# SCH_touch_clock_2022-06-03.net
KiCad netlist of a schematic drawn in EasyEDA
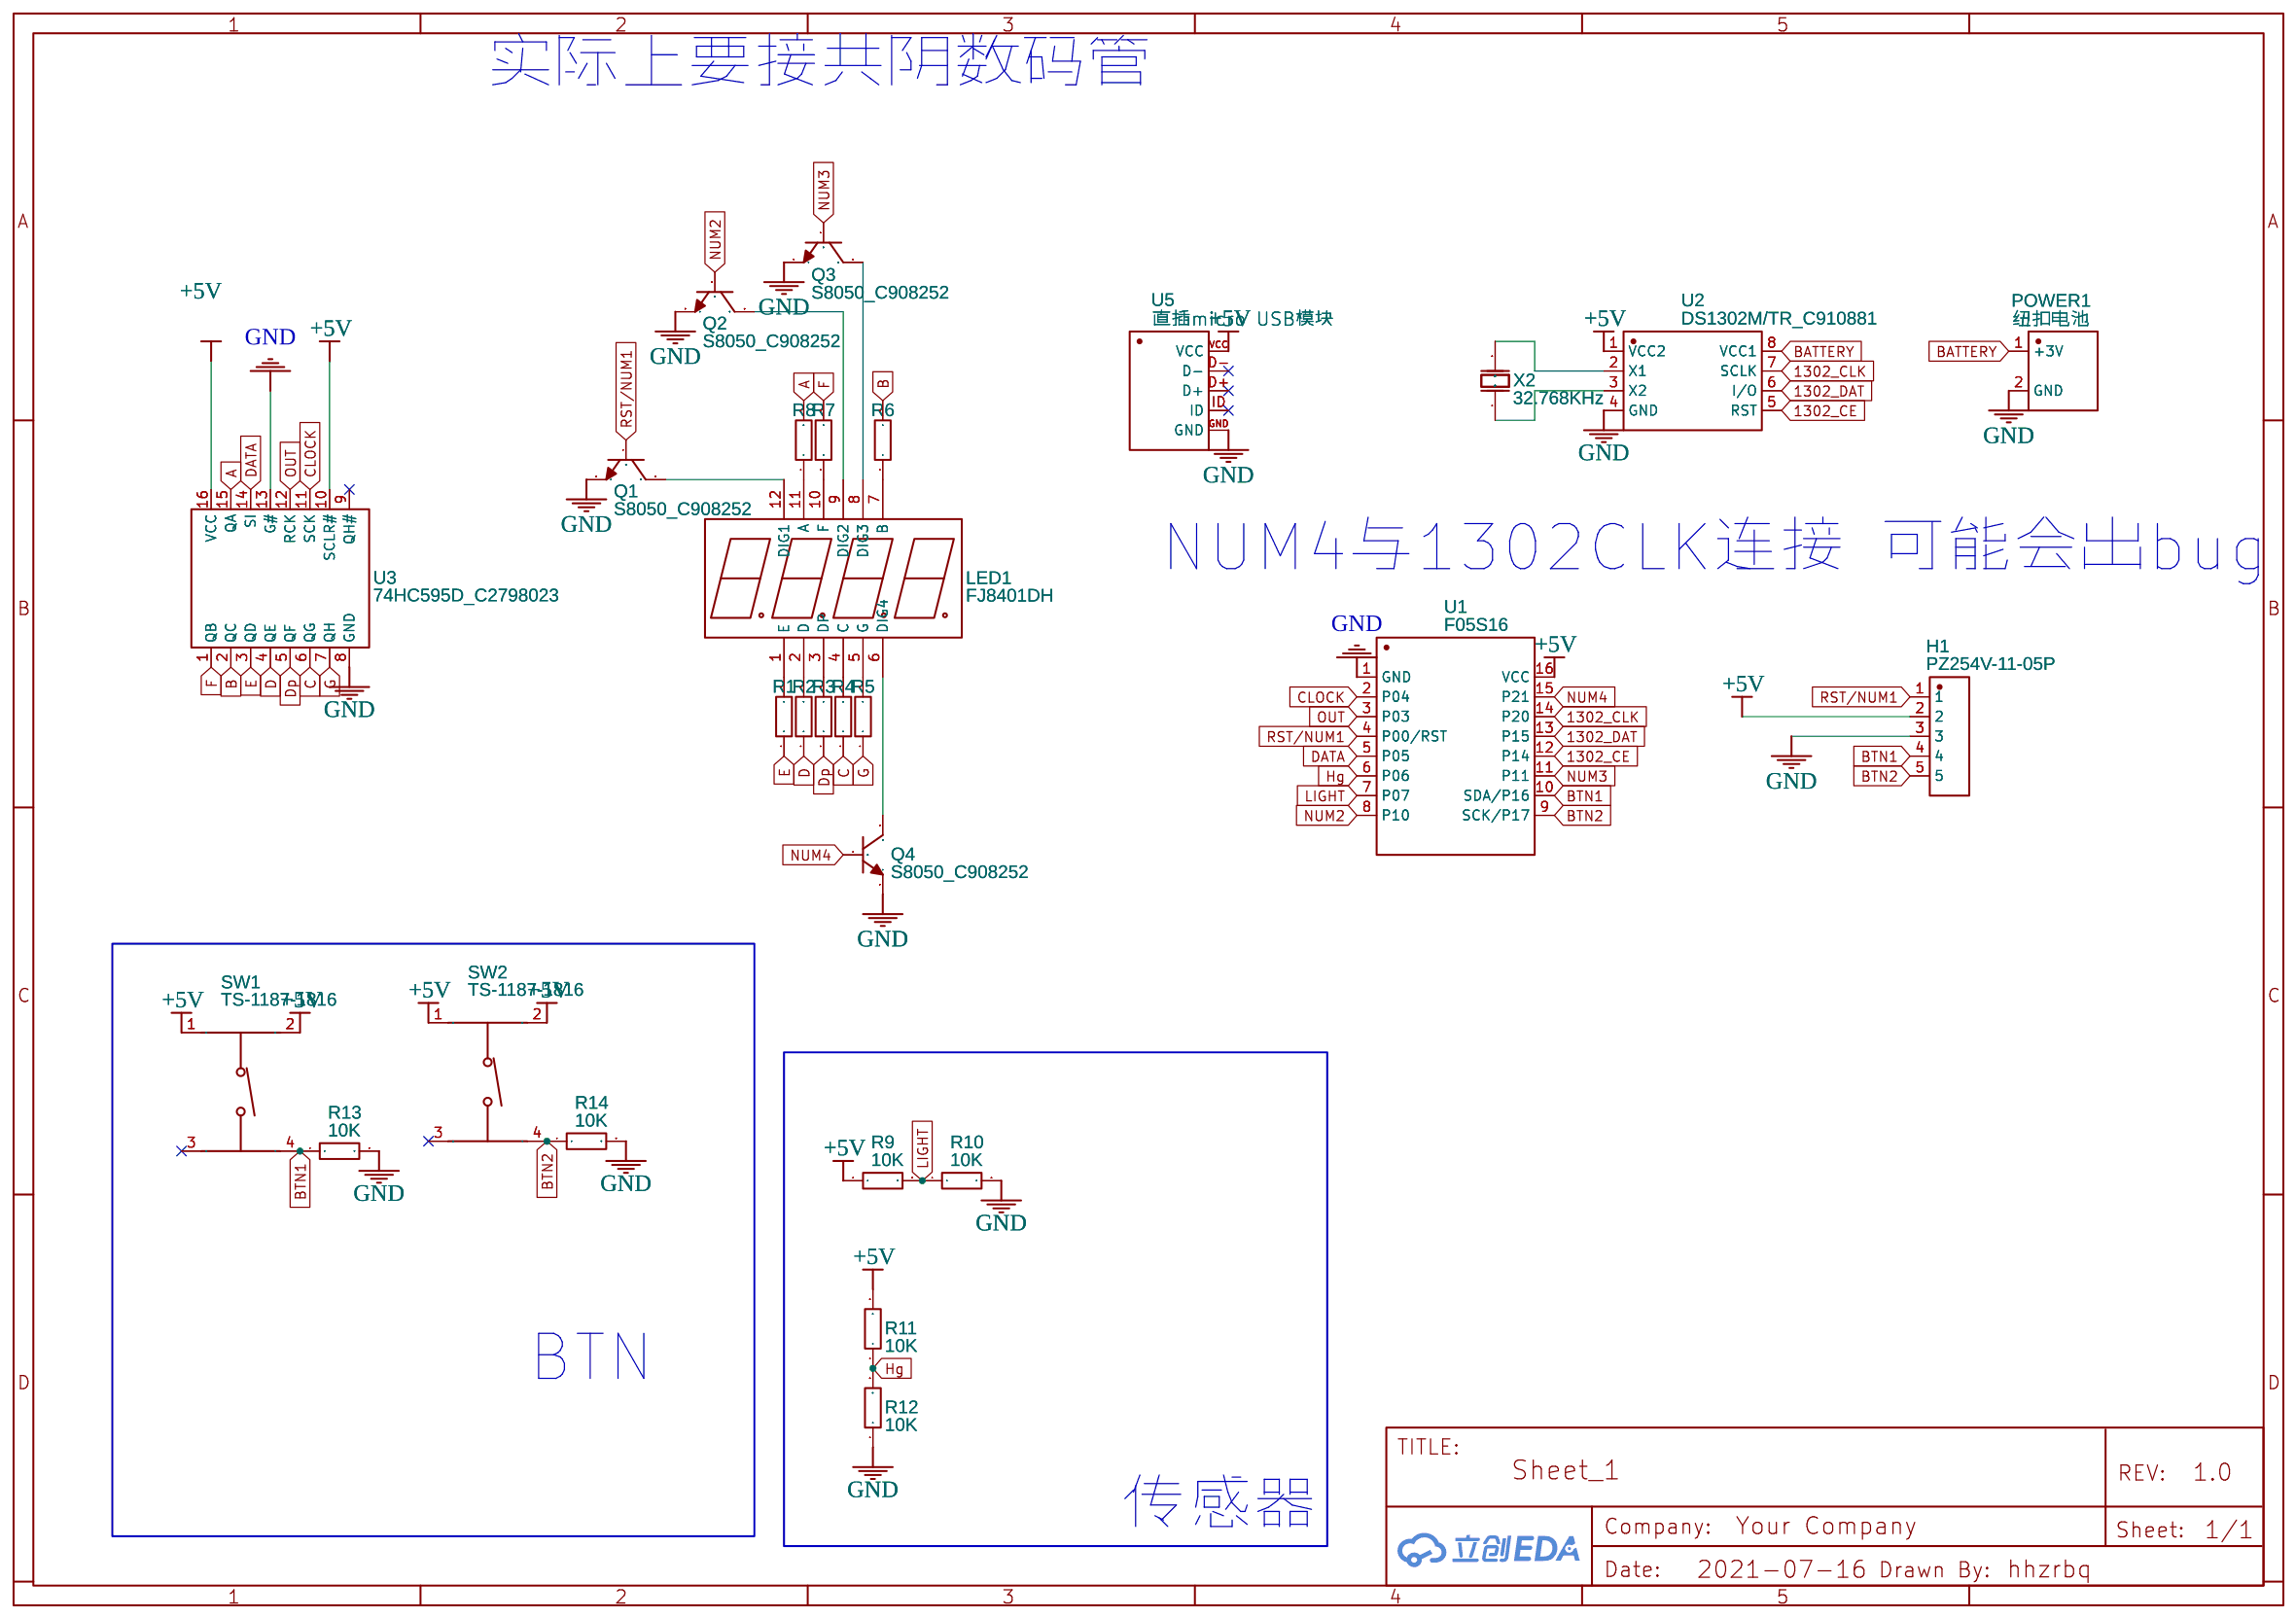
[diagram p0: schematic sheet]

(export (version "E")
  (design (tool "Eeschema 10.0.6"))
  (components
    (comp (ref "H1")
      (value "PZ254V-11-05P")
      (fields (field (name "BOM_Supplier Part") "C492404"))
      (libsource (lib "") (part "PZ254V-11-05P"))
    )
    (comp (ref "LED1")
      (value "FJ8401DH")
      (fields (field (name "BOM_Supplier Part") "C70368"))
      (libsource (lib "") (part "FJ8401DH"))
    )
    (comp (ref "POWER1") (value "纽扣电池") (libsource (lib "") (part "纽扣电池")))
    (comp (ref "Q1")
      (value "S8050_C908252")
      (fields (field (name "BOM_Manufacturer Part") "S8050") (field (name "BOM_Supplier Part") "C908252"))
      (libsource (lib "") (part "S8050_C908252"))
    )
    (comp (ref "Q2")
      (value "S8050_C908252")
      (fields (field (name "BOM_Manufacturer Part") "S8050") (field (name "BOM_Supplier Part") "C908252"))
      (libsource (lib "") (part "S8050_C908252"))
    )
    (comp (ref "Q3")
      (value "S8050_C908252")
      (fields (field (name "BOM_Manufacturer Part") "S8050") (field (name "BOM_Supplier Part") "C908252"))
      (libsource (lib "") (part "S8050_C908252"))
    )
    (comp (ref "Q4")
      (value "S8050_C908252")
      (fields (field (name "BOM_Manufacturer Part") "S8050") (field (name "BOM_Supplier Part") "C908252"))
      (libsource (lib "") (part "S8050_C908252_1"))
    )
    (comp (ref "R1")
      (value "10K")
      (fields
        (field (name "BOM_Manufacturer Part") "RG2012P-103-B-T5")
        (field (name "BOM_Supplier Part") "C328719")
      )
      (libsource (lib "") (part "RG2012P-103-B-T5"))
    )
    (comp (ref "R2")
      (value "10K")
      (fields
        (field (name "BOM_Manufacturer Part") "RG2012P-103-B-T5")
        (field (name "BOM_Supplier Part") "C328719")
      )
      (libsource (lib "") (part "RG2012P-103-B-T5"))
    )
    (comp (ref "R3")
      (value "10K")
      (fields
        (field (name "BOM_Manufacturer Part") "RG2012P-103-B-T5")
        (field (name "BOM_Supplier Part") "C328719")
      )
      (libsource (lib "") (part "RG2012P-103-B-T5"))
    )
    (comp (ref "R4")
      (value "10K")
      (fields
        (field (name "BOM_Manufacturer Part") "RG2012P-103-B-T5")
        (field (name "BOM_Supplier Part") "C328719")
      )
      (libsource (lib "") (part "RG2012P-103-B-T5"))
    )
    (comp (ref "R5")
      (value "10K")
      (fields
        (field (name "BOM_Manufacturer Part") "RG2012P-103-B-T5")
        (field (name "BOM_Supplier Part") "C328719")
      )
      (libsource (lib "") (part "RG2012P-103-B-T5"))
    )
    (comp (ref "R6")
      (value "10K")
      (fields
        (field (name "BOM_Manufacturer Part") "RG2012P-103-B-T5")
        (field (name "BOM_Supplier Part") "C328719")
      )
      (libsource (lib "") (part "RG2012P-103-B-T5"))
    )
    (comp (ref "R7")
      (value "10K")
      (fields
        (field (name "BOM_Manufacturer Part") "RG2012P-103-B-T5")
        (field (name "BOM_Supplier Part") "C328719")
      )
      (libsource (lib "") (part "RG2012P-103-B-T5"))
    )
    (comp (ref "R8")
      (value "10K")
      (fields
        (field (name "BOM_Manufacturer Part") "RG2012P-103-B-T5")
        (field (name "BOM_Supplier Part") "C328719")
      )
      (libsource (lib "") (part "RG2012P-103-B-T5"))
    )
    (comp (ref "R9")
      (value "10K")
      (fields
        (field (name "BOM_Manufacturer Part") "RG2012P-103-B-T5")
        (field (name "BOM_Supplier Part") "C328719")
      )
      (libsource (lib "") (part "RG2012P-103-B-T5_1"))
    )
    (comp (ref "R10")
      (value "10K")
      (fields
        (field (name "BOM_Manufacturer Part") "RG2012P-103-B-T5")
        (field (name "BOM_Supplier Part") "C328719")
      )
      (libsource (lib "") (part "RG2012P-103-B-T5_1"))
    )
    (comp (ref "R11")
      (value "10K")
      (fields
        (field (name "BOM_Manufacturer Part") "RG2012P-103-B-T5")
        (field (name "BOM_Supplier Part") "C328719")
      )
      (libsource (lib "") (part "RG2012P-103-B-T5"))
    )
    (comp (ref "R12")
      (value "10K")
      (fields
        (field (name "BOM_Manufacturer Part") "RG2012P-103-B-T5")
        (field (name "BOM_Supplier Part") "C328719")
      )
      (libsource (lib "") (part "RG2012P-103-B-T5"))
    )
    (comp (ref "R13")
      (value "10K")
      (fields
        (field (name "BOM_Manufacturer Part") "RG2012P-103-B-T5")
        (field (name "BOM_Supplier Part") "C328719")
      )
      (libsource (lib "") (part "RG2012P-103-B-T5_1"))
    )
    (comp (ref "R14")
      (value "10K")
      (fields
        (field (name "BOM_Manufacturer Part") "RG2012P-103-B-T5")
        (field (name "BOM_Supplier Part") "C328719")
      )
      (libsource (lib "") (part "RG2012P-103-B-T5_1"))
    )
    (comp (ref "SW1")
      (value "TS-1187-1816")
      (fields (field (name "BOM_Supplier Part") "C183614"))
      (libsource (lib "") (part "TS-1187-1816"))
    )
    (comp (ref "SW2")
      (value "TS-1187-1816")
      (fields (field (name "BOM_Supplier Part") "C183614"))
      (libsource (lib "") (part "TS-1187-1816"))
    )
    (comp (ref "U1") (value "F05S16") (libsource (lib "") (part "F05S16")))
    (comp (ref "U2")
      (value "DS1302M/TR_C910881")
      (fields
        (field (name "BOM_Manufacturer Part") "DS1302M/TR")
        (field (name "BOM_Supplier Part") "C910881")
      )
      (libsource (lib "") (part "DS1302M/TR_C910881"))
    )
    (comp (ref "U3")
      (value "74HC595D_C2798023")
      (fields (field (name "BOM_Manufacturer Part") "74HC595D") (field (name "BOM_Supplier Part") "C2798023"))
      (libsource (lib "") (part "74HC595D_C2798023"))
    )
    (comp (ref "U5") (value "直插micro USB模块") (libsource (lib "") (part "直插micro USB模块")))
    (comp (ref "X2")
      (value "32.768KHz")
      (fields
        (field (name "BOM_Manufacturer Part") "AB38T-32.768KHZ")
        (field (name "BOM_Supplier Part") "C194002")
      )
      (libsource (lib "") (part "AB38T-32.768KHZ"))
    )
  )
  (nets
    (net (code "1") (name "+5V") (class "Default")
      (node (ref "H1") (pin "2") (pinfunction "2_2") (pintype "unspecified"))
      (node (ref "R11") (pin "2") (pinfunction "2_2") (pintype "input"))
      (node (ref "R9") (pin "1") (pinfunction "1_1") (pintype "input"))
      (node (ref "SW1") (pin "1") (pinfunction "1_1") (pintype "unspecified"))
      (node (ref "SW1") (pin "2") (pinfunction "2_2") (pintype "unspecified"))
      (node (ref "SW2") (pin "1") (pinfunction "1_1") (pintype "unspecified"))
      (node (ref "SW2") (pin "2") (pinfunction "2_2") (pintype "unspecified"))
      (node (ref "U1") (pin "16") (pinfunction "VCC_16") (pintype "passive"))
      (node (ref "U2") (pin "1") (pinfunction "VCC2_1") (pintype "unspecified"))
      (node (ref "U3") (pin "10") (pinfunction "SCLR#_10") (pintype "unspecified"))
      (node (ref "U3") (pin "16") (pinfunction "VCC_16") (pintype "unspecified"))
      (node (ref "U5") (pin "VCC") (pinfunction "VCC_VCC") (pintype "unspecified"))
    )
    (net (code "2") (name "1302_CE") (class "Default")
      (node (ref "U1") (pin "12") (pinfunction "P14_12") (pintype "bidirectional"))
      (node (ref "U2") (pin "5") (pinfunction "RST_5") (pintype "unspecified"))
    )
    (net (code "3") (name "1302_CLK") (class "Default")
      (node (ref "U1") (pin "14") (pinfunction "P20_14") (pintype "bidirectional"))
      (node (ref "U2") (pin "7") (pinfunction "SCLK_7") (pintype "unspecified"))
    )
    (net (code "4") (name "1302_DAT") (class "Default")
      (node (ref "U1") (pin "13") (pinfunction "P15_13") (pintype "bidirectional"))
      (node (ref "U2") (pin "6") (pinfunction "I/O_6") (pintype "unspecified"))
    )
    (net (code "5") (name "A") (class "Default")
      (node (ref "R8") (pin "2") (pinfunction "2_2") (pintype "input"))
      (node (ref "U3") (pin "15") (pinfunction "QA_15") (pintype "unspecified"))
    )
    (net (code "6") (name "B") (class "Default")
      (node (ref "R6") (pin "2") (pinfunction "2_2") (pintype "input"))
      (node (ref "U3") (pin "2") (pinfunction "QC_2") (pintype "unspecified"))
    )
    (net (code "7") (name "BATTERY") (class "Default")
      (node (ref "POWER1") (pin "1") (pinfunction "+3V_1") (pintype "unspecified"))
      (node (ref "U2") (pin "8") (pinfunction "VCC1_8") (pintype "unspecified"))
    )
    (net (code "8") (name "BTN1") (class "Default")
      (node (ref "H1") (pin "4") (pinfunction "4_4") (pintype "unspecified"))
      (node (ref "R13") (pin "1") (pinfunction "1_1") (pintype "input"))
      (node (ref "SW1") (pin "4") (pinfunction "4_4") (pintype "unspecified"))
      (node (ref "U1") (pin "10") (pinfunction "SDA/P16_10") (pintype "bidirectional"))
    )
    (net (code "9") (name "BTN2") (class "Default")
      (node (ref "H1") (pin "5") (pinfunction "5_5") (pintype "unspecified"))
      (node (ref "R14") (pin "1") (pinfunction "1_1") (pintype "input"))
      (node (ref "SW2") (pin "4") (pinfunction "4_4") (pintype "unspecified"))
      (node (ref "U1") (pin "9") (pinfunction "SCK/P17_9") (pintype "bidirectional"))
    )
    (net (code "10") (name "C") (class "Default")
      (node (ref "R4") (pin "1") (pinfunction "1_1") (pintype "input"))
      (node (ref "U3") (pin "6") (pinfunction "QG_6") (pintype "unspecified"))
    )
    (net (code "11") (name "CLOCK") (class "Default")
      (node (ref "U1") (pin "2") (pinfunction "P04_2") (pintype "bidirectional"))
      (node (ref "U3") (pin "11") (pinfunction "SCK_11") (pintype "unspecified"))
    )
    (net (code "12") (name "D") (class "Default")
      (node (ref "R2") (pin "1") (pinfunction "1_1") (pintype "input"))
      (node (ref "U3") (pin "4") (pinfunction "QE_4") (pintype "unspecified"))
    )
    (net (code "13") (name "DATA") (class "Default")
      (node (ref "U1") (pin "5") (pinfunction "P05_5") (pintype "bidirectional"))
      (node (ref "U3") (pin "14") (pinfunction "SI_14") (pintype "unspecified"))
    )
    (net (code "14") (name "Dp") (class "Default")
      (node (ref "R3") (pin "1") (pinfunction "1_1") (pintype "input"))
      (node (ref "U3") (pin "5") (pinfunction "QF_5") (pintype "unspecified"))
    )
    (net (code "15") (name "E") (class "Default")
      (node (ref "R1") (pin "1") (pinfunction "1_1") (pintype "input"))
      (node (ref "U3") (pin "3") (pinfunction "QD_3") (pintype "unspecified"))
    )
    (net (code "16") (name "F") (class "Default")
      (node (ref "R7") (pin "2") (pinfunction "2_2") (pintype "input"))
      (node (ref "U3") (pin "1") (pinfunction "QB_1") (pintype "unspecified"))
    )
    (net (code "17") (name "G") (class "Default")
      (node (ref "R5") (pin "1") (pinfunction "1_1") (pintype "input"))
      (node (ref "U3") (pin "7") (pinfunction "QH_7") (pintype "unspecified"))
    )
    (net (code "18") (name "GND") (class "Default")
      (node (ref "H1") (pin "3") (pinfunction "3_3") (pintype "unspecified"))
      (node (ref "POWER1") (pin "2") (pinfunction "GND_2") (pintype "unspecified"))
      (node (ref "Q1") (pin "2") (pinfunction "E_2") (pintype "input"))
      (node (ref "Q2") (pin "2") (pinfunction "E_2") (pintype "input"))
      (node (ref "Q3") (pin "2") (pinfunction "E_2") (pintype "input"))
      (node (ref "Q4") (pin "2") (pinfunction "E_2") (pintype "input"))
      (node (ref "R10") (pin "2") (pinfunction "2_2") (pintype "input"))
      (node (ref "R12") (pin "1") (pinfunction "1_1") (pintype "input"))
      (node (ref "R13") (pin "2") (pinfunction "2_2") (pintype "input"))
      (node (ref "R14") (pin "2") (pinfunction "2_2") (pintype "input"))
      (node (ref "U1") (pin "1") (pinfunction "GND_1") (pintype "passive"))
      (node (ref "U2") (pin "4") (pinfunction "GND_4") (pintype "unspecified"))
      (node (ref "U3") (pin "13") (pinfunction "G#_13") (pintype "unspecified"))
      (node (ref "U3") (pin "8") (pinfunction "GND_8") (pintype "unspecified"))
      (node (ref "U5") (pin "GND") (pinfunction "GND_GND") (pintype "unspecified"))
    )
    (net (code "19") (name "Hg") (class "Default")
      (node (ref "R11") (pin "1") (pinfunction "1_1") (pintype "input"))
      (node (ref "R12") (pin "2") (pinfunction "2_2") (pintype "input"))
      (node (ref "U1") (pin "6") (pinfunction "P06_6") (pintype "bidirectional"))
    )
    (net (code "20") (name "LIGHT") (class "Default")
      (node (ref "R10") (pin "1") (pinfunction "1_1") (pintype "input"))
      (node (ref "R9") (pin "2") (pinfunction "2_2") (pintype "input"))
      (node (ref "U1") (pin "7") (pinfunction "P07_7") (pintype "bidirectional"))
    )
    (net (code "21") (name "NUM2") (class "Default")
      (node (ref "Q2") (pin "1") (pinfunction "B_1") (pintype "input"))
      (node (ref "U1") (pin "8") (pinfunction "P10_8") (pintype "bidirectional"))
    )
    (net (code "22") (name "NUM3") (class "Default")
      (node (ref "Q3") (pin "1") (pinfunction "B_1") (pintype "input"))
      (node (ref "U1") (pin "11") (pinfunction "P11_11") (pintype "bidirectional"))
    )
    (net (code "23") (name "NUM4") (class "Default")
      (node (ref "Q4") (pin "1") (pinfunction "B_1") (pintype "input"))
      (node (ref "U1") (pin "15") (pinfunction "P21_15") (pintype "bidirectional"))
    )
    (net (code "24") (name "Net-(LED1-A)") (class "Default")
      (node (ref "LED1") (pin "11") (pinfunction "A_11") (pintype "unspecified"))
      (node (ref "R8") (pin "1") (pinfunction "1_1") (pintype "input"))
    )
    (net (code "25") (name "Net-(LED1-B)") (class "Default")
      (node (ref "LED1") (pin "7") (pinfunction "B_7") (pintype "unspecified"))
      (node (ref "R6") (pin "1") (pinfunction "1_1") (pintype "input"))
    )
    (net (code "26") (name "Net-(LED1-C)") (class "Default")
      (node (ref "LED1") (pin "4") (pinfunction "C_4") (pintype "unspecified"))
      (node (ref "R4") (pin "2") (pinfunction "2_2") (pintype "input"))
    )
    (net (code "27") (name "Net-(LED1-D)") (class "Default")
      (node (ref "LED1") (pin "2") (pinfunction "D_2") (pintype "unspecified"))
      (node (ref "R2") (pin "2") (pinfunction "2_2") (pintype "input"))
    )
    (net (code "28") (name "Net-(LED1-DIG1)") (class "Default")
      (node (ref "LED1") (pin "12") (pinfunction "DIG1_12") (pintype "unspecified"))
      (node (ref "Q1") (pin "3") (pinfunction "C_3") (pintype "input"))
    )
    (net (code "29") (name "Net-(LED1-DIG2)") (class "Default")
      (node (ref "LED1") (pin "9") (pinfunction "DIG2_9") (pintype "unspecified"))
      (node (ref "Q2") (pin "3") (pinfunction "C_3") (pintype "input"))
    )
    (net (code "30") (name "Net-(LED1-DIG3)") (class "Default")
      (node (ref "LED1") (pin "8") (pinfunction "DIG3_8") (pintype "unspecified"))
      (node (ref "Q3") (pin "3") (pinfunction "C_3") (pintype "input"))
    )
    (net (code "31") (name "Net-(LED1-DIG4)") (class "Default")
      (node (ref "LED1") (pin "6") (pinfunction "DIG4_6") (pintype "unspecified"))
      (node (ref "Q4") (pin "3") (pinfunction "C_3") (pintype "input"))
    )
    (net (code "32") (name "Net-(LED1-DP)") (class "Default")
      (node (ref "LED1") (pin "3") (pinfunction "DP_3") (pintype "unspecified"))
      (node (ref "R3") (pin "2") (pinfunction "2_2") (pintype "input"))
    )
    (net (code "33") (name "Net-(LED1-E)") (class "Default")
      (node (ref "LED1") (pin "1") (pinfunction "E_1") (pintype "unspecified"))
      (node (ref "R1") (pin "2") (pinfunction "2_2") (pintype "input"))
    )
    (net (code "34") (name "Net-(LED1-F)") (class "Default")
      (node (ref "LED1") (pin "10") (pinfunction "F_10") (pintype "unspecified"))
      (node (ref "R7") (pin "1") (pinfunction "1_1") (pintype "input"))
    )
    (net (code "35") (name "Net-(LED1-G)") (class "Default")
      (node (ref "LED1") (pin "5") (pinfunction "G_5") (pintype "unspecified"))
      (node (ref "R5") (pin "2") (pinfunction "2_2") (pintype "input"))
    )
    (net (code "36") (name "Net-(U2-X1)") (class "Default")
      (node (ref "U2") (pin "2") (pinfunction "X1_2") (pintype "unspecified"))
      (node (ref "X2") (pin "2") (pinfunction "OSC2_2") (pintype "input"))
    )
    (net (code "37") (name "Net-(U2-X2)") (class "Default")
      (node (ref "U2") (pin "3") (pinfunction "X2_3") (pintype "unspecified"))
      (node (ref "X2") (pin "1") (pinfunction "OSC1_1") (pintype "input"))
    )
    (net (code "38") (name "OUT") (class "Default")
      (node (ref "U1") (pin "3") (pinfunction "P03_3") (pintype "bidirectional"))
      (node (ref "U3") (pin "12") (pinfunction "RCK_12") (pintype "unspecified"))
    )
    (net (code "39") (name "RST{slash}NUM1") (class "Default")
      (node (ref "H1") (pin "1") (pinfunction "1_1") (pintype "unspecified"))
      (node (ref "Q1") (pin "1") (pinfunction "B_1") (pintype "input"))
      (node (ref "U1") (pin "4") (pinfunction "P00/RST_4") (pintype "bidirectional"))
    )
    (net (code "40") (name "unconnected-(SW1-Pad3)") (class "Default")
      (node (ref "SW1") (pin "3") (pinfunction "3_3") (pintype "unspecified+no_connect"))
    )
    (net (code "41") (name "unconnected-(SW2-Pad3)") (class "Default")
      (node (ref "SW2") (pin "3") (pinfunction "3_3") (pintype "unspecified+no_connect"))
    )
    (net (code "42") (name "unconnected-(U3-QH#-Pad9)") (class "Default")
      (node (ref "U3") (pin "9") (pinfunction "QH#_9") (pintype "unspecified+no_connect"))
    )
    (net (code "43") (name "unconnected-(U5-PadD+)") (class "Default")
      (node (ref "U5") (pin "D+") (pinfunction "D+_D+") (pintype "unspecified+no_connect"))
    )
    (net (code "44") (name "unconnected-(U5-PadD-)") (class "Default")
      (node (ref "U5") (pin "D-") (pinfunction "D-_D-") (pintype "unspecified+no_connect"))
    )
    (net (code "45") (name "unconnected-(U5-PadID)") (class "Default")
      (node (ref "U5") (pin "ID") (pinfunction "ID_ID") (pintype "unspecified+no_connect"))
    )
  )
)
